# EXTADC.net
KiCad netlist of a schematic drawn in Altium Designer
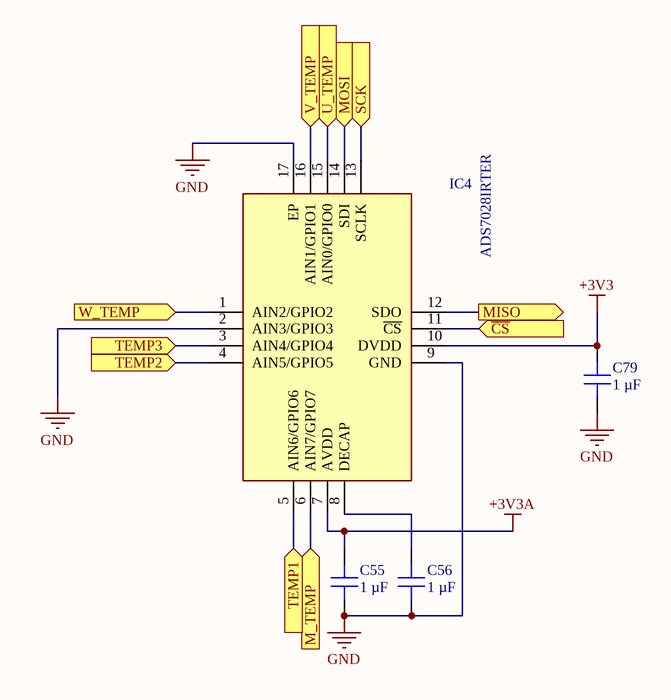
[diagram p0: EXTADC.SchDoc]

(export (version "E")
  (design (tool "Eeschema 10.0.6"))
  (components
    (comp (ref "C55")
      (value "1 µF")
      (footprint "MURATA GRM155 0402_1005")
      (description "CAP CER 1UF 10V X7S 0402")
      (fields
        (field (name "PART NUMBER") "GRM155C71A105KE11D")
        (field (name "CAPACITANCE") "1 µF")
        (field (name "MANUFACTURER") "Murata Electronics")
      )
      (libsource (lib "Celestial Altium Library - altium_library") (part "Capacitor"))
    )
    (comp (ref "C56")
      (value "1 µF")
      (footprint "MURATA GRM155 0402_1005")
      (description "CAP CER 1UF 10V X7S 0402")
      (fields
        (field (name "PART NUMBER") "GRM155C71A105KE11D")
        (field (name "CAPACITANCE") "1 µF")
        (field (name "MANUFACTURER") "Murata Electronics")
      )
      (libsource (lib "Celestial Altium Library - altium_library") (part "Capacitor"))
    )
    (comp (ref "C79")
      (value "1 µF")
      (footprint "MURATA GRM155 0402_1005")
      (description "CAP CER 1UF 10V X7S 0402")
      (fields
        (field (name "PART NUMBER") "GRM155C71A105KE11D")
        (field (name "CAPACITANCE") "1 µF")
        (field (name "MANUFACTURER") "Murata Electronics")
      )
      (libsource (lib "Celestial Altium Library - altium_library") (part "Capacitor"))
    )
    (comp (ref "IC4")
      (value "ADS7028IRTER")
      (footprint "PcbLib1:QFN50P300X300X80-17N-D")
      (description "Integrated Circuit")
      (fields (field (name "MOUSER PART NUMBER") "595-ADS7028IRTER"))
      (libsource (lib "*") (part "ADS7028IRTER"))
    )
  )
  (nets
    (net (code "1") (name "+3V3") (class "Default")
      (node (ref "C79") (pin "2") (pinfunction "2_2") (pintype "passive"))
      (node (ref "IC4") (pin "10") (pinfunction "DVDD_10") (pintype "passive"))
    )
    (net (code "2") (name "+3V3A") (class "Default")
      (node (ref "C55") (pin "2") (pinfunction "2_2") (pintype "passive"))
      (node (ref "IC4") (pin "7") (pinfunction "AVDD_7") (pintype "passive"))
    )
    (net (code "3") (name "/MISO") (class "Default")
      (node (ref "IC4") (pin "12") (pinfunction "SDO_12") (pintype "passive"))
    )
    (net (code "4") (name "/MOSI") (class "Default")
      (node (ref "IC4") (pin "14") (pinfunction "SDI_14") (pintype "passive"))
    )
    (net (code "5") (name "/M_TEMP") (class "Default")
      (node (ref "IC4") (pin "6") (pinfunction "AIN7/GPIO7_6") (pintype "passive"))
    )
    (net (code "6") (name "/SCK") (class "Default")
      (node (ref "IC4") (pin "13") (pinfunction "SCLK_13") (pintype "passive"))
    )
    (net (code "7") (name "/TEMP1") (class "Default")
      (node (ref "IC4") (pin "5") (pinfunction "AIN6/GPIO6_5") (pintype "passive"))
    )
    (net (code "8") (name "/TEMP2") (class "Default")
      (node (ref "IC4") (pin "4") (pinfunction "AIN5/GPIO5_4") (pintype "passive"))
    )
    (net (code "9") (name "/TEMP3") (class "Default")
      (node (ref "IC4") (pin "3") (pinfunction "AIN4/GPIO4_3") (pintype "passive"))
    )
    (net (code "10") (name "/U_TEMP") (class "Default")
      (node (ref "IC4") (pin "15") (pinfunction "AIN0/GPIO0_15") (pintype "passive"))
    )
    (net (code "11") (name "/V_TEMP") (class "Default")
      (node (ref "IC4") (pin "16") (pinfunction "AIN1/GPIO1_16") (pintype "passive"))
    )
    (net (code "12") (name "/W_TEMP") (class "Default")
      (node (ref "IC4") (pin "1") (pinfunction "AIN2/GPIO2_1") (pintype "passive"))
    )
    (net (code "13") (name "/~{CS}") (class "Default")
      (node (ref "IC4") (pin "11") (pinfunction "~{CS}_11") (pintype "passive"))
    )
    (net (code "14") (name "GND") (class "Default")
      (node (ref "C55") (pin "1") (pinfunction "1_1") (pintype "passive"))
      (node (ref "C56") (pin "1") (pinfunction "1_1") (pintype "passive"))
      (node (ref "C79") (pin "1") (pinfunction "1_1") (pintype "passive"))
      (node (ref "IC4") (pin "17") (pinfunction "EP_17") (pintype "passive"))
      (node (ref "IC4") (pin "2") (pinfunction "AIN3/GPIO3_2") (pintype "passive"))
      (node (ref "IC4") (pin "9") (pinfunction "GND_9") (pintype "passive"))
    )
    (net (code "15") (name "Net-(IC4-DECAP)") (class "Default")
      (node (ref "C56") (pin "2") (pinfunction "2_2") (pintype "passive"))
      (node (ref "IC4") (pin "8") (pinfunction "DECAP_8") (pintype "passive"))
    )
  )
)
